# SCH_ZeeShield_-_GW_Zb_Shield_For_ESP32_E.net
KiCad netlist of a schematic drawn in EasyEDA
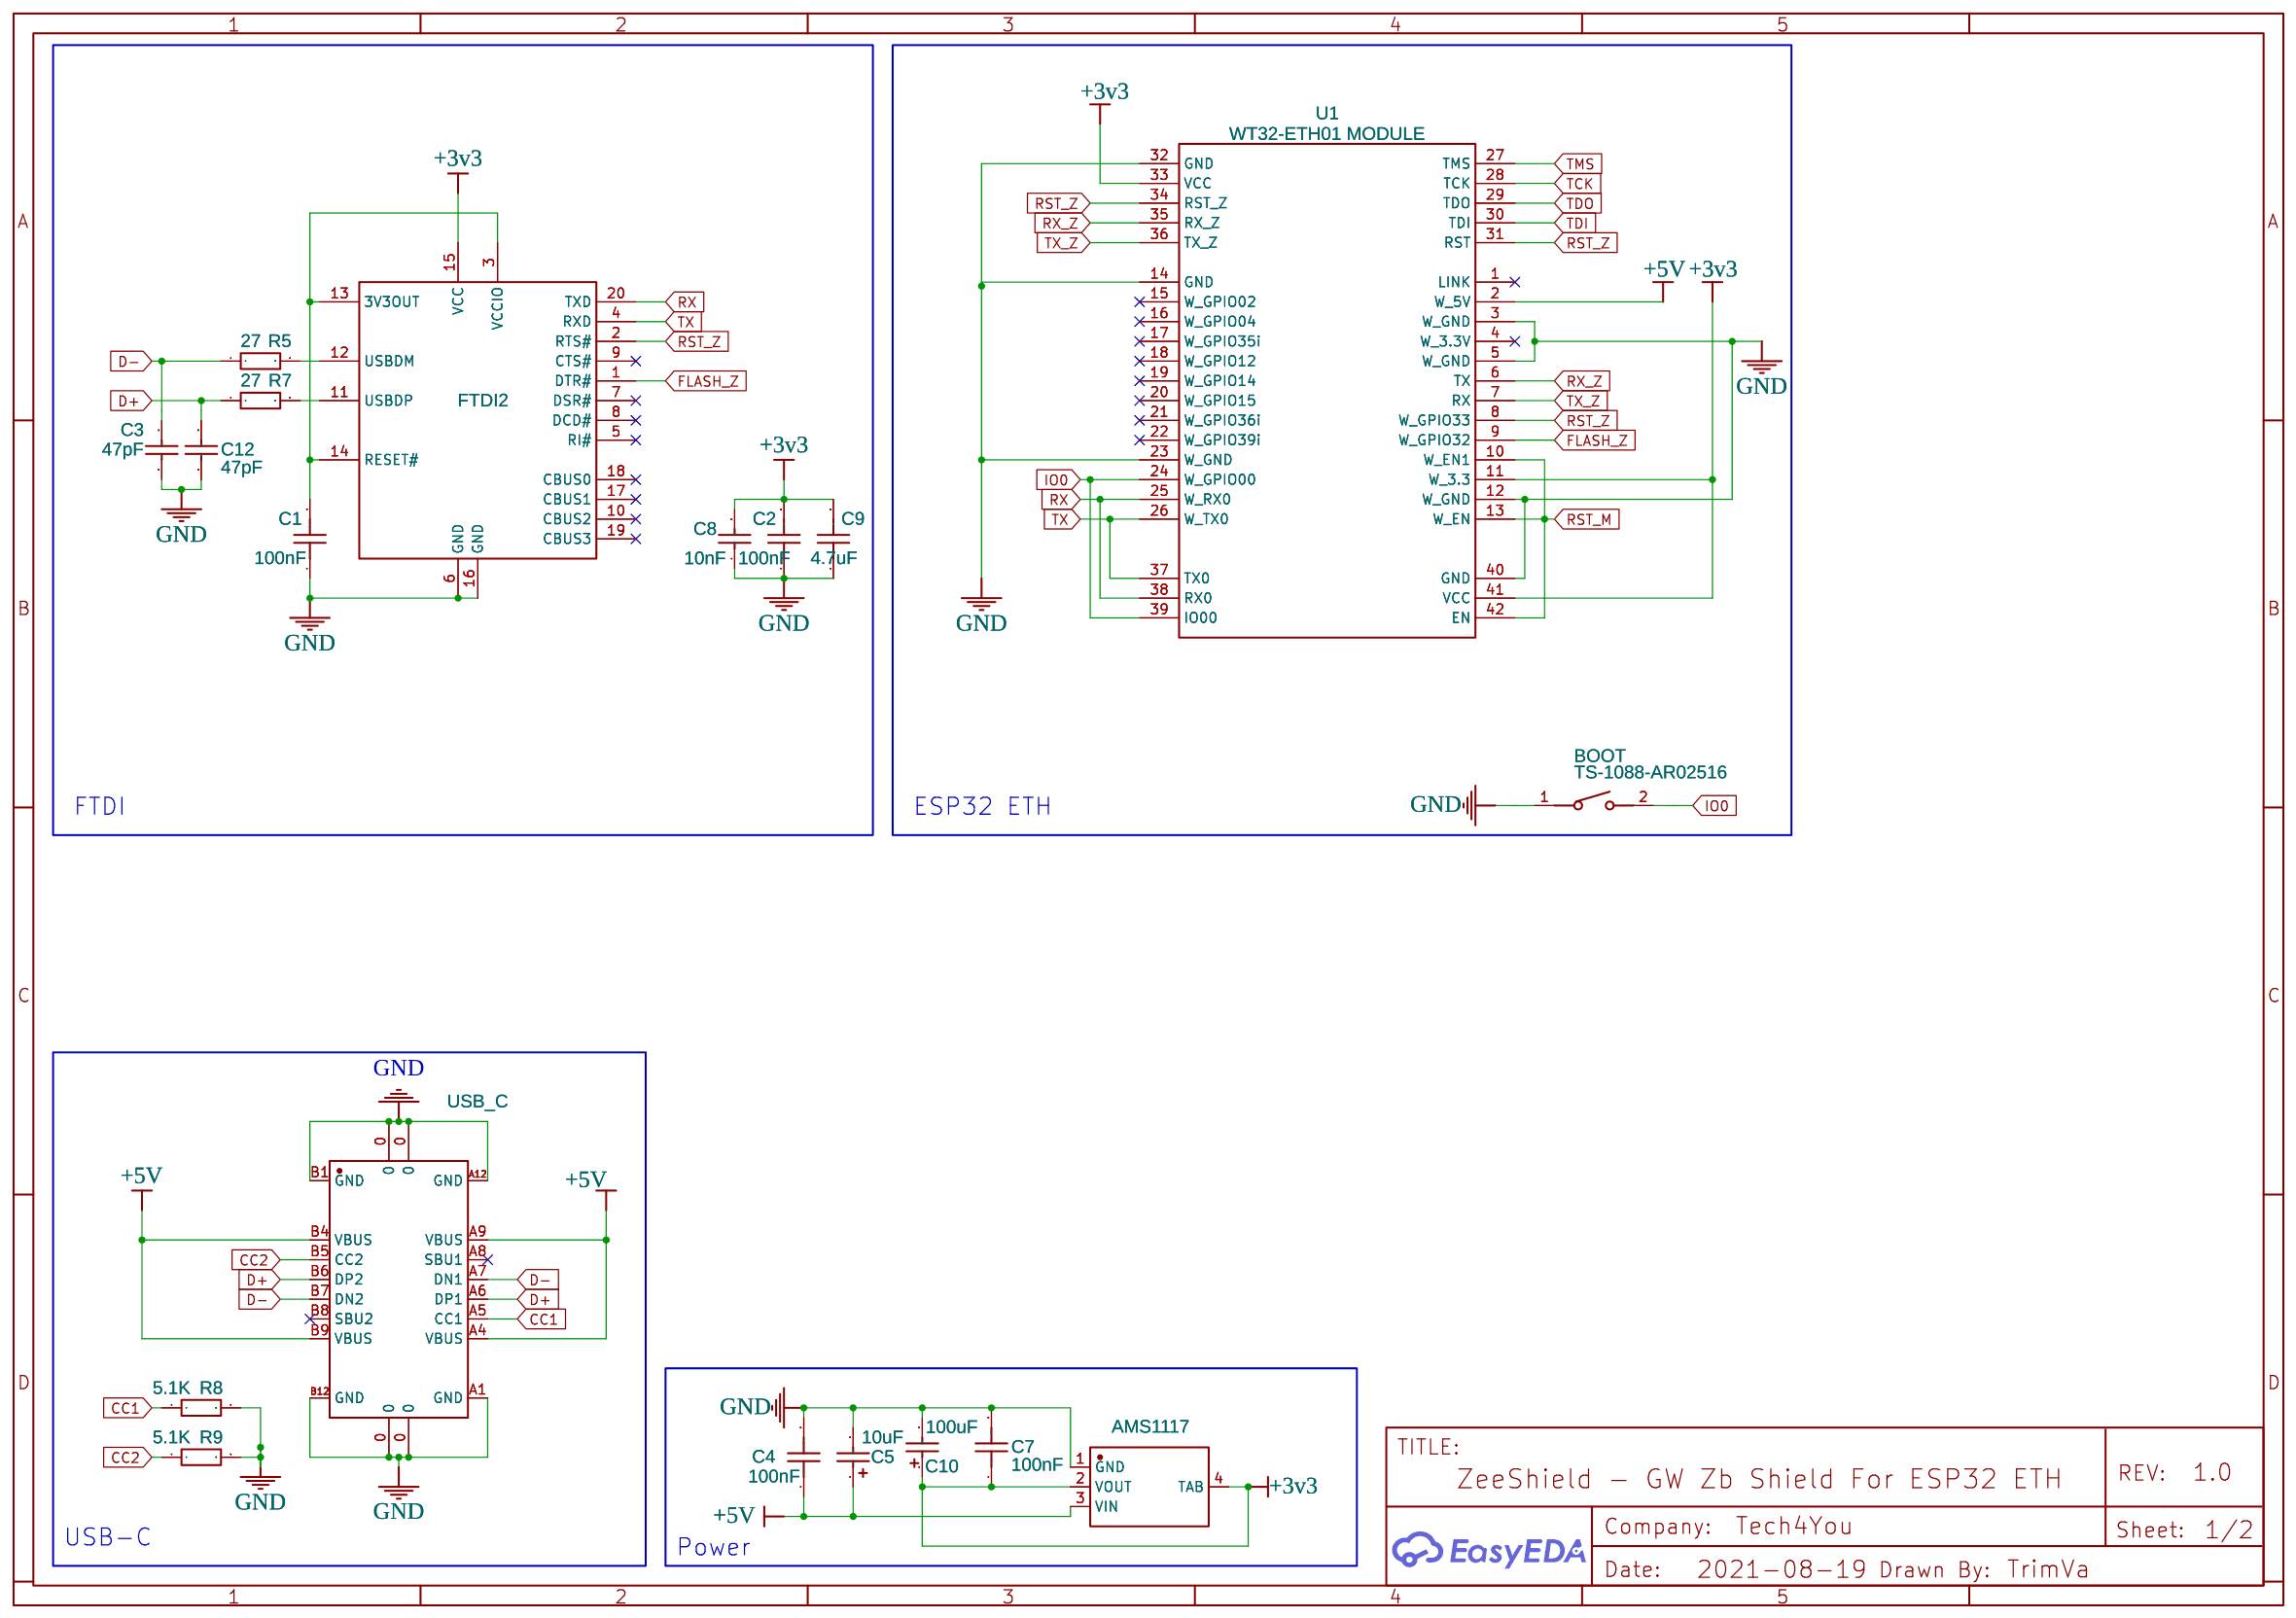
[diagram p0: Main]
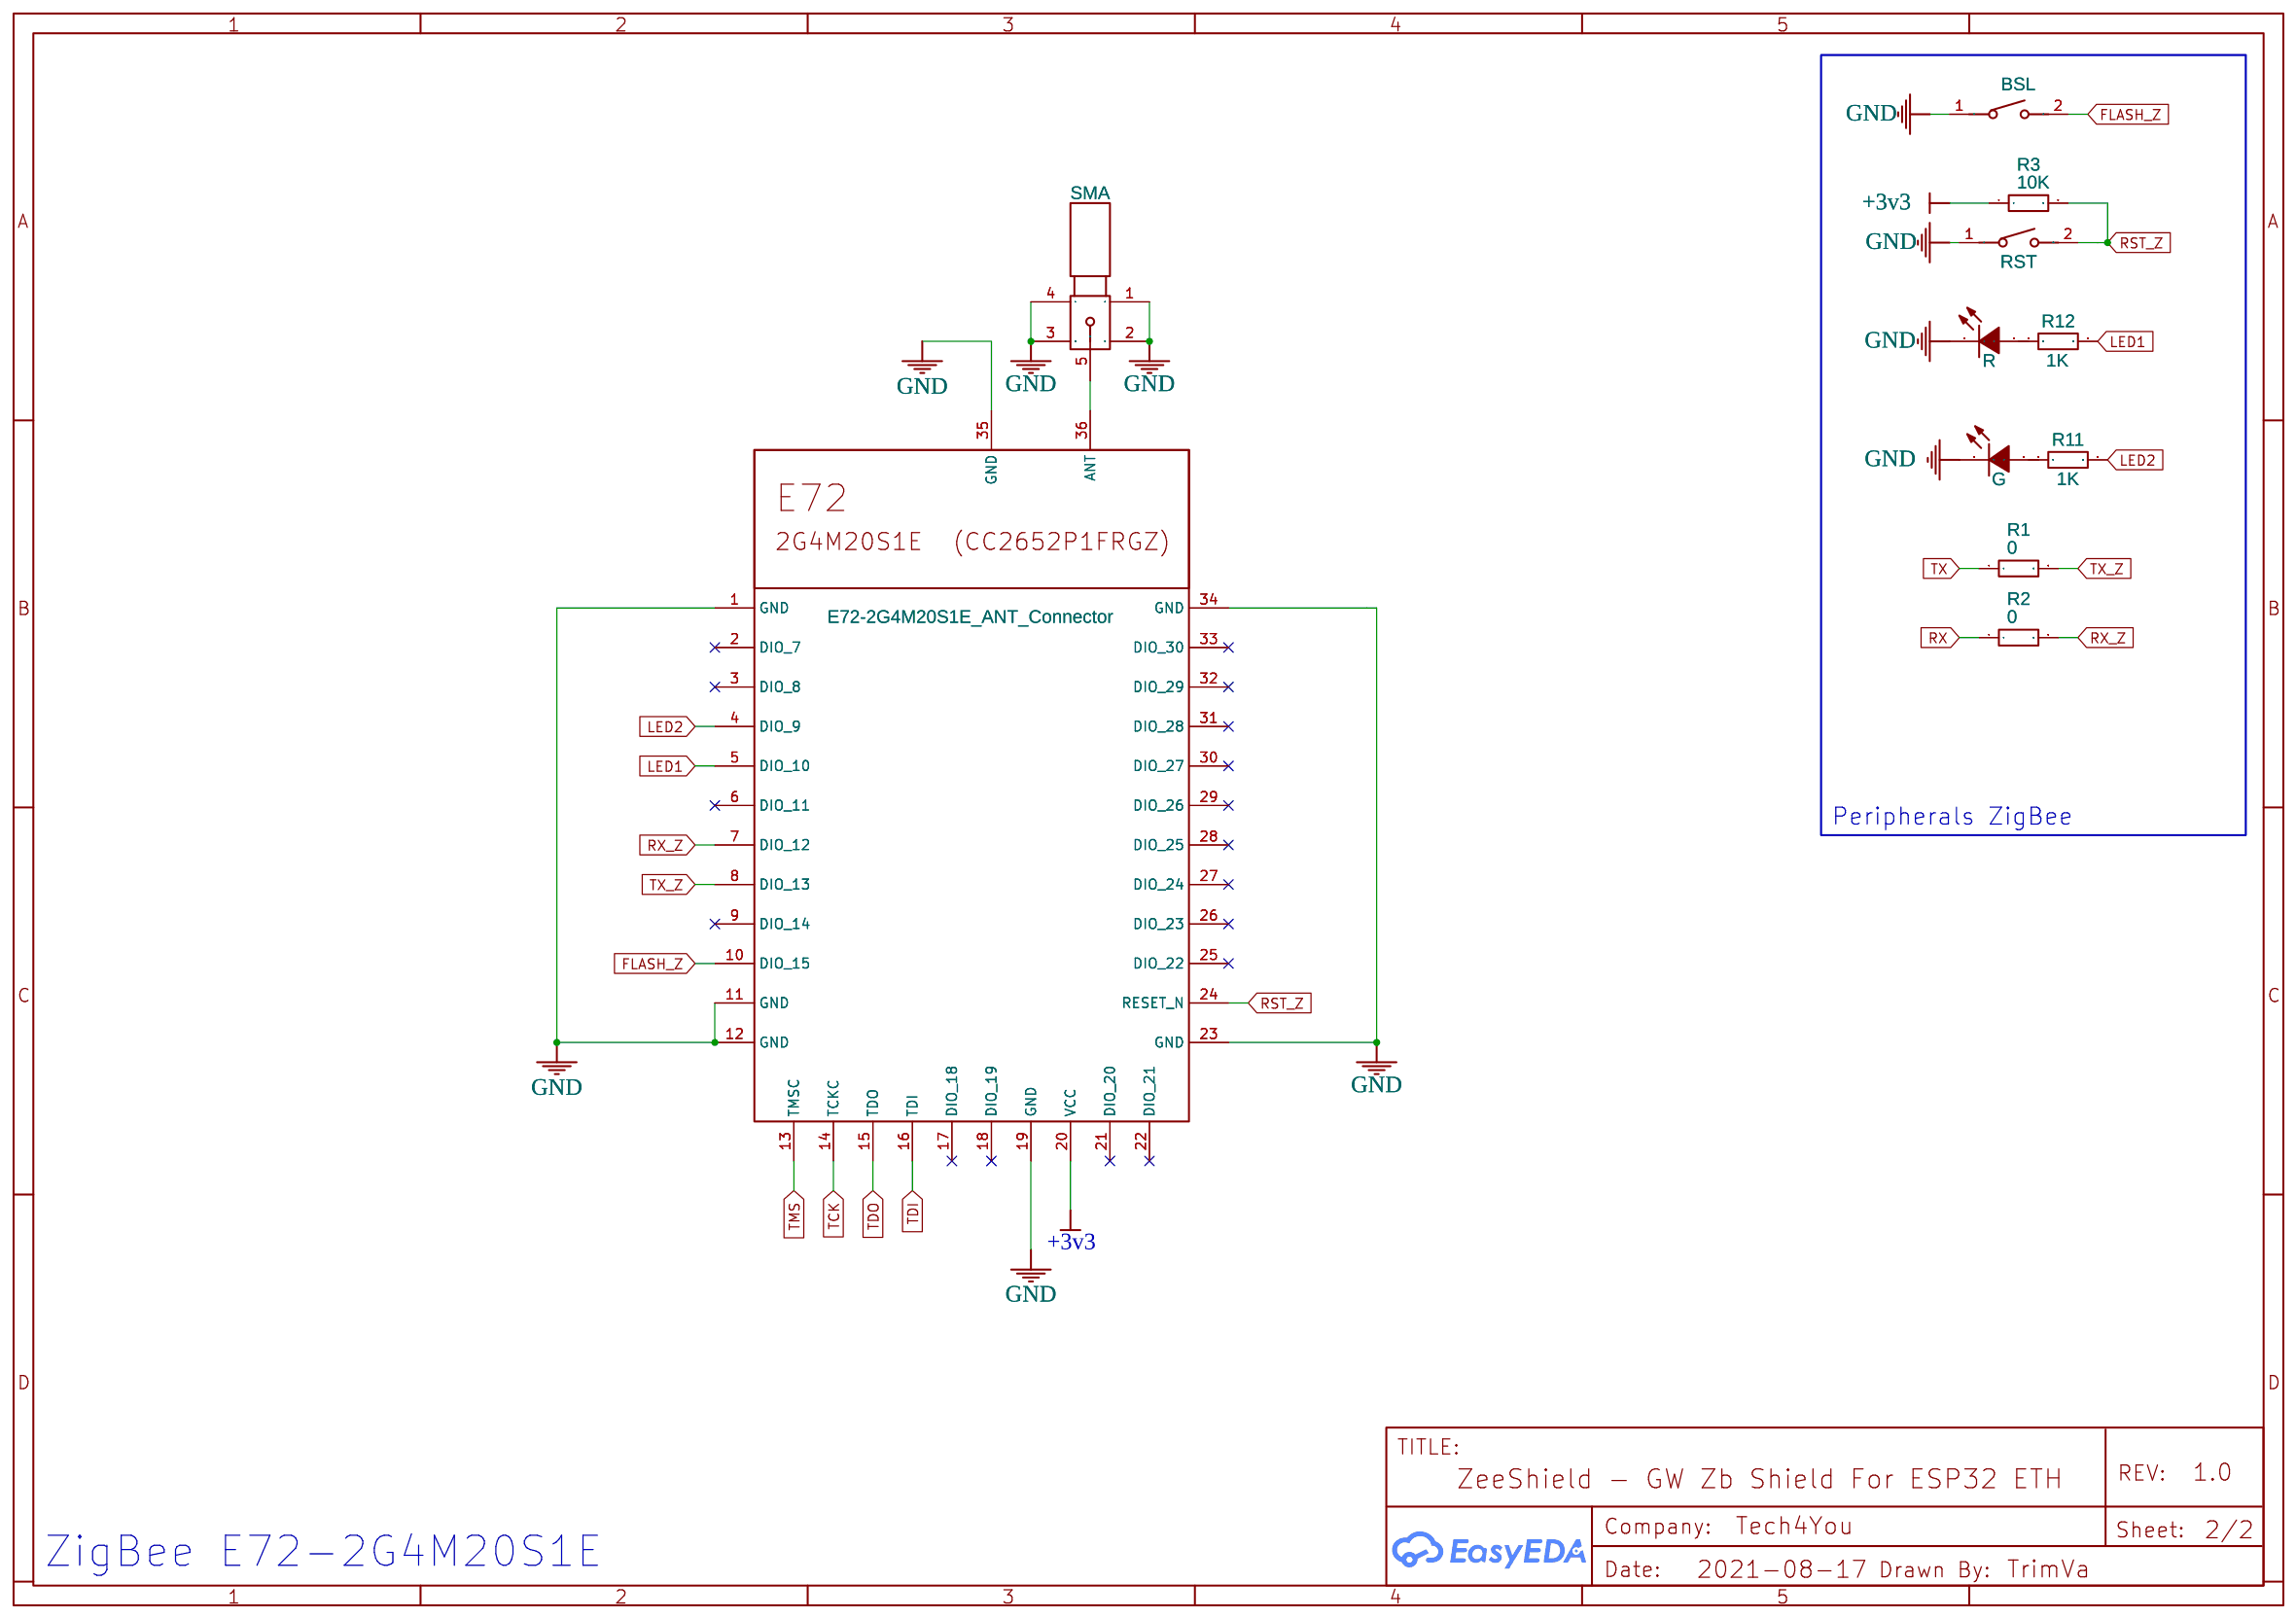
[diagram p1: ZigBee]

(export (version "E")
  (design (tool "Eeschema 10.0.6"))
  (components
    (comp (ref "AMS1117")
      (value "AMS1117-3.3_C351784")
      (fields
        (field (name "BOM_Manufacturer Part") "AMS1117-3.3")
        (field (name "BOM_Supplier Part") "C351784")
      )
      (libsource (lib "") (part "AMS1117-3.3_C351784"))
    )
    (comp (ref "BOOT")
      (value "TS-1088-AR02516")
      (fields (field (name "BOM_Supplier Part") "C720478"))
      (libsource (lib "") (part "TS-1088-AR02516"))
    )
    (comp (ref "C1")
      (value "100nF")
      (fields
        (field (name "BOM_Manufacturer Part") "TCC0402X7R104K160AT")
        (field (name "BOM_Supplier Part") "C392963")
      )
      (libsource (lib "") (part "TCC0402X7R104K160AT"))
    )
    (comp (ref "C2")
      (value "100nF")
      (fields
        (field (name "BOM_Manufacturer Part") "TCC0402X7R104K160AT")
        (field (name "BOM_Supplier Part") "C392963")
      )
      (libsource (lib "") (part "TCC0402X7R104K160AT"))
    )
    (comp (ref "C3")
      (value "47pF")
      (fields
        (field (name "BOM_Manufacturer Part") "CC0402JRNPO9BN470")
        (field (name "BOM_Supplier Part") "C60137")
      )
      (libsource (lib "") (part "CC0402JRNPO9BN470"))
    )
    (comp (ref "C4")
      (value "100nF")
      (fields
        (field (name "BOM_Manufacturer Part") "TCC0402X7R104K160AT")
        (field (name "BOM_Supplier Part") "C392963")
      )
      (libsource (lib "") (part "TCC0402X7R104K160AT"))
    )
    (comp (ref "C5")
      (value "10uF")
      (fields
        (field (name "BOM_Manufacturer Part") "TAJA106K016RNJ")
        (field (name "BOM_Supplier Part") "C7171")
      )
      (libsource (lib "") (part "TAJA106K016RNJ"))
    )
    (comp (ref "C7")
      (value "100nF")
      (fields
        (field (name "BOM_Manufacturer Part") "TCC0402X7R104K160AT")
        (field (name "BOM_Supplier Part") "C392963")
      )
      (libsource (lib "") (part "TCC0402X7R104K160AT"))
    )
    (comp (ref "C8")
      (value "10nF")
      (fields
        (field (name "BOM_Manufacturer Part") "CC0402KRX7R9BB103")
        (field (name "BOM_Supplier Part") "C60133")
      )
      (libsource (lib "") (part "CC0402KRX7R9BB103"))
    )
    (comp (ref "C9")
      (value "4.7uF")
      (fields
        (field (name "BOM_Manufacturer Part") "CL05A475MQ5NRNC")
        (field (name "BOM_Supplier Part") "C307423")
      )
      (libsource (lib "") (part "CL05A475MQ5NRNC_C307423"))
    )
    (comp (ref "C10")
      (value "100uF")
      (fields
        (field (name "BOM_Manufacturer Part") "T490A107M006ATE800")
        (field (name "BOM_Supplier Part") "C122251")
      )
      (libsource (lib "") (part "T490A107M006ATE800"))
    )
    (comp (ref "C12")
      (value "47pF")
      (fields
        (field (name "BOM_Manufacturer Part") "CC0402JRNPO9BN470")
        (field (name "BOM_Supplier Part") "C60137")
      )
      (libsource (lib "") (part "CC0402JRNPO9BN470"))
    )
    (comp (ref "FTDI2")
      (value "FT231XS-R")
      (fields (field (name "BOM_Supplier Part") "C132160"))
      (libsource (lib "") (part "FT231XS-R"))
    )
    (comp (ref "R5")
      (value "27")
      (fields
        (field (name "BOM_Manufacturer Part") "0402WGJ0270TCE")
        (field (name "BOM_Supplier Part") "C25156")
      )
      (libsource (lib "") (part "0402WGJ0270TCE"))
    )
    (comp (ref "R7")
      (value "27")
      (fields
        (field (name "BOM_Manufacturer Part") "0402WGJ0270TCE")
        (field (name "BOM_Supplier Part") "C25156")
      )
      (libsource (lib "") (part "0402WGJ0270TCE"))
    )
    (comp (ref "R8")
      (value "5.1K")
      (fields
        (field (name "BOM_Manufacturer Part") "RC-02W512JT")
        (field (name "BOM_Supplier Part") "C258132")
      )
      (libsource (lib "") (part "RC-02W512JT"))
    )
    (comp (ref "R9")
      (value "5.1K")
      (fields
        (field (name "BOM_Manufacturer Part") "RC-02W512JT")
        (field (name "BOM_Supplier Part") "C258132")
      )
      (libsource (lib "") (part "RC-02W512JT"))
    )
    (comp (ref "U1")
      (value "WT32-ETH01 MODULE")
      (fields (field (name "BOM_Manufacturer Part") "WT32-ETH01"))
      (libsource (lib "") (part "WT32-ETH01 MODULE"))
    )
    (comp (ref "USB_C")
      (value "TYPE-C-31-M-12")
      (fields (field (name "BOM_Supplier Part") "C165948"))
      (libsource (lib "") (part "TYPE-C-31-M-12"))
    )
    (comp (ref "BSL")
      (value "TS-1088-AR02516")
      (fields (field (name "BOM_Supplier Part") "C720478"))
      (libsource (lib "") (part "TS-1088-AR02516_1"))
    )
    (comp (ref "G")
      (value "G")
      (fields
        (field (name "BOM_Manufacturer Part") "0805G (Green)")
        (field (name "BOM_Supplier Part") "C2297")
      )
      (libsource (lib "") (part "0805G (Green)"))
    )
    (comp (ref "GND1")
      (value "E72-2G4M20S1E_ANT_Connector")
      (fields
        (field (name "BOM_Manufacturer Part") "CC2652P1FRGZ")
        (field (name "BOM_Supplier Part") "E72-2G4M20S1E")
      )
      (libsource (lib "") (part "E72-2G4M20S1E_ANT_Connector"))
    )
    (comp (ref "R")
      (value "R")
      (fields
        (field (name "BOM_Manufacturer Part") "FC-2012HRK-620D")
        (field (name "BOM_Supplier Part") "C84256")
      )
      (libsource (lib "") (part "FC-2012HRK-620D"))
    )
    (comp (ref "R1")
      (value "0")
      (fields
        (field (name "BOM_Manufacturer Part") "RTT02000JTH")
        (field (name "BOM_Supplier Part") "C102746")
      )
      (libsource (lib "") (part "RTT02000JTH"))
    )
    (comp (ref "R2")
      (value "0")
      (fields
        (field (name "BOM_Manufacturer Part") "RTT02000JTH")
        (field (name "BOM_Supplier Part") "C102746")
      )
      (libsource (lib "") (part "RTT02000JTH"))
    )
    (comp (ref "R3")
      (value "10K")
      (fields
        (field (name "BOM_Manufacturer Part") "RC-02W103JT")
        (field (name "BOM_Supplier Part") "C140214")
      )
      (libsource (lib "") (part "RC-02W103JT_C140214"))
    )
    (comp (ref "R11")
      (value "1K")
      (fields
        (field (name "BOM_Manufacturer Part") "0402WGF1001TCE")
        (field (name "BOM_Supplier Part") "C11702")
      )
      (libsource (lib "") (part "0402WGF1001TCE"))
    )
    (comp (ref "R12")
      (value "1K")
      (fields
        (field (name "BOM_Manufacturer Part") "0402WGF1001TCE")
        (field (name "BOM_Supplier Part") "C11702")
      )
      (libsource (lib "") (part "0402WGF1001TCE"))
    )
    (comp (ref "RST")
      (value "TS-1088-AR02516")
      (fields (field (name "BOM_Supplier Part") "C720478"))
      (libsource (lib "") (part "TS-1088-AR02516"))
    )
    (comp (ref "SMA")
      (value "BWSMA-KE-P001")
      (fields (field (name "BOM_Supplier Part") "C496550"))
      (libsource (lib "") (part "BWSMA-KE-P001"))
    )
  )
  (nets
    (net (code "1") (name "+3v3") (class "Default")
      (node (ref "AMS1117") (pin "2") (pinfunction "VOUT_2") (pintype "unspecified"))
      (node (ref "AMS1117") (pin "4") (pinfunction "TAB_4") (pintype "unspecified"))
      (node (ref "C10") (pin "1") (pinfunction "1_1") (pintype "input"))
      (node (ref "C2") (pin "2") (pinfunction "2_2") (pintype "unspecified"))
      (node (ref "C7") (pin "1") (pinfunction "1_1") (pintype "unspecified"))
      (node (ref "C8") (pin "2") (pinfunction "2_2") (pintype "input"))
      (node (ref "C9") (pin "2") (pinfunction "2_2") (pintype "unspecified"))
      (node (ref "FTDI2") (pin "15") (pinfunction "VCC_15") (pintype "passive"))
      (node (ref "GND1") (pin "20") (pinfunction "VCC_20") (pintype "unspecified"))
      (node (ref "R3") (pin "1") (pinfunction "1_1") (pintype "unspecified"))
      (node (ref "U1") (pin "11") (pinfunction "W_3.3_11") (pintype "unspecified"))
      (node (ref "U1") (pin "33") (pinfunction "VCC_33") (pintype "unspecified"))
      (node (ref "U1") (pin "41") (pinfunction "VCC_41") (pintype "unspecified"))
    )
    (net (code "2") (name "+5V") (class "Default")
      (node (ref "AMS1117") (pin "3") (pinfunction "VIN_3") (pintype "unspecified"))
      (node (ref "C4") (pin "1") (pinfunction "1_1") (pintype "unspecified"))
      (node (ref "C5") (pin "1") (pinfunction "1_1") (pintype "input"))
      (node (ref "U1") (pin "2") (pinfunction "W_5V_2") (pintype "unspecified"))
      (node (ref "USB_C") (pin "A4") (pinfunction "VBUS_A4") (pintype "unspecified"))
      (node (ref "USB_C") (pin "A9") (pinfunction "VBUS_A9") (pintype "unspecified"))
      (node (ref "USB_C") (pin "B4") (pinfunction "VBUS_B4") (pintype "unspecified"))
      (node (ref "USB_C") (pin "B9") (pinfunction "VBUS_B9") (pintype "unspecified"))
    )
    (net (code "3") (name "CC1") (class "Default")
      (node (ref "R8") (pin "1") (pinfunction "1_1") (pintype "unspecified"))
      (node (ref "USB_C") (pin "A5") (pinfunction "CC1_A5") (pintype "unspecified"))
    )
    (net (code "4") (name "CC2") (class "Default")
      (node (ref "R9") (pin "1") (pinfunction "1_1") (pintype "unspecified"))
      (node (ref "USB_C") (pin "B5") (pinfunction "CC2_B5") (pintype "unspecified"))
    )
    (net (code "5") (name "D+") (class "Default")
      (node (ref "C12") (pin "2") (pinfunction "2_2") (pintype "input"))
      (node (ref "R7") (pin "1") (pinfunction "1_1") (pintype "input"))
      (node (ref "USB_C") (pin "A6") (pinfunction "DP1_A6") (pintype "unspecified"))
      (node (ref "USB_C") (pin "B6") (pinfunction "DP2_B6") (pintype "unspecified"))
    )
    (net (code "6") (name "D-") (class "Default")
      (node (ref "C3") (pin "2") (pinfunction "2_2") (pintype "input"))
      (node (ref "R5") (pin "1") (pinfunction "1_1") (pintype "input"))
      (node (ref "USB_C") (pin "A7") (pinfunction "DN1_A7") (pintype "unspecified"))
      (node (ref "USB_C") (pin "B7") (pinfunction "DN2_B7") (pintype "unspecified"))
    )
    (net (code "7") (name "FLASH_Z") (class "Default")
      (node (ref "BSL") (pin "2") (pinfunction "2_2") (pintype "unspecified"))
      (node (ref "FTDI2") (pin "1") (pinfunction "DTR#_1") (pintype "output"))
      (node (ref "GND1") (pin "10") (pinfunction "DIO_15_10") (pintype "unspecified"))
      (node (ref "U1") (pin "9") (pinfunction "W_GPIO32_9") (pintype "unspecified"))
    )
    (net (code "8") (name "GND") (class "Default")
      (node (ref "AMS1117") (pin "1") (pinfunction "GND_1") (pintype "unspecified"))
      (node (ref "BOOT") (pin "1") (pinfunction "1_1") (pintype "unspecified"))
      (node (ref "BSL") (pin "1") (pinfunction "1_1") (pintype "unspecified"))
      (node (ref "C1") (pin "1") (pinfunction "1_1") (pintype "unspecified"))
      (node (ref "C10") (pin "2") (pinfunction "2_2") (pintype "input"))
      (node (ref "C12") (pin "1") (pinfunction "1_1") (pintype "input"))
      (node (ref "C2") (pin "1") (pinfunction "1_1") (pintype "unspecified"))
      (node (ref "C3") (pin "1") (pinfunction "1_1") (pintype "input"))
      (node (ref "C4") (pin "2") (pinfunction "2_2") (pintype "unspecified"))
      (node (ref "C5") (pin "2") (pinfunction "2_2") (pintype "input"))
      (node (ref "C7") (pin "2") (pinfunction "2_2") (pintype "unspecified"))
      (node (ref "C8") (pin "1") (pinfunction "1_1") (pintype "input"))
      (node (ref "C9") (pin "1") (pinfunction "1_1") (pintype "unspecified"))
      (node (ref "FTDI2") (pin "16") (pinfunction "GND_16") (pintype "passive"))
      (node (ref "FTDI2") (pin "6") (pinfunction "GND_6") (pintype "passive"))
      (node (ref "G") (pin "1") (pinfunction "K_1") (pintype "unspecified"))
      (node (ref "GND1") (pin "1") (pinfunction "GND_1") (pintype "unspecified"))
      (node (ref "GND1") (pin "11") (pinfunction "GND_11") (pintype "unspecified"))
      (node (ref "GND1") (pin "12") (pinfunction "GND_12") (pintype "unspecified"))
      (node (ref "GND1") (pin "19") (pinfunction "GND_19") (pintype "unspecified"))
      (node (ref "GND1") (pin "23") (pinfunction "GND_23") (pintype "unspecified"))
      (node (ref "GND1") (pin "34") (pinfunction "GND_34") (pintype "unspecified"))
      (node (ref "GND1") (pin "35") (pinfunction "GND_35") (pintype "unspecified"))
      (node (ref "R") (pin "1") (pinfunction "-_1") (pintype "unspecified"))
      (node (ref "R8") (pin "2") (pinfunction "2_2") (pintype "unspecified"))
      (node (ref "R9") (pin "2") (pinfunction "2_2") (pintype "unspecified"))
      (node (ref "RST") (pin "1") (pinfunction "1_1") (pintype "unspecified"))
      (node (ref "SMA") (pin "1") (pinfunction "1_1") (pintype "unspecified"))
      (node (ref "SMA") (pin "2") (pinfunction "2_2") (pintype "unspecified"))
      (node (ref "SMA") (pin "3") (pinfunction "3_3") (pintype "unspecified"))
      (node (ref "SMA") (pin "4") (pinfunction "4_4") (pintype "unspecified"))
      (node (ref "U1") (pin "12") (pinfunction "W_GND_12") (pintype "unspecified"))
      (node (ref "U1") (pin "14") (pinfunction "GND_14") (pintype "unspecified"))
      (node (ref "U1") (pin "23") (pinfunction "W_GND_23") (pintype "unspecified"))
      (node (ref "U1") (pin "3") (pinfunction "W_GND_3") (pintype "unspecified"))
      (node (ref "U1") (pin "32") (pinfunction "GND_32") (pintype "unspecified"))
      (node (ref "U1") (pin "40") (pinfunction "GND_40") (pintype "unspecified"))
      (node (ref "U1") (pin "5") (pinfunction "W_GND_5") (pintype "unspecified"))
      (node (ref "USB_C") (pin "0") (pinfunction "0_0") (pintype "unspecified"))
      (node (ref "USB_C") (pin "A1") (pinfunction "GND_A1") (pintype "unspecified"))
      (node (ref "USB_C") (pin "A12") (pinfunction "GND_A12") (pintype "unspecified"))
      (node (ref "USB_C") (pin "B1") (pinfunction "GND_B1") (pintype "unspecified"))
      (node (ref "USB_C") (pin "B12") (pinfunction "GND_B12") (pintype "unspecified"))
    )
    (net (code "9") (name "IO0") (class "Default")
      (node (ref "BOOT") (pin "2") (pinfunction "2_2") (pintype "unspecified"))
      (node (ref "U1") (pin "24") (pinfunction "W_GPIO00_24") (pintype "unspecified"))
      (node (ref "U1") (pin "39") (pinfunction "IO00_39") (pintype "unspecified"))
    )
    (net (code "10") (name "LED1") (class "Default")
      (node (ref "GND1") (pin "5") (pinfunction "DIO_10_5") (pintype "unspecified"))
      (node (ref "R12") (pin "2") (pinfunction "2_2") (pintype "input"))
    )
    (net (code "11") (name "LED2") (class "Default")
      (node (ref "GND1") (pin "4") (pinfunction "DIO_9_4") (pintype "unspecified"))
      (node (ref "R11") (pin "2") (pinfunction "2_2") (pintype "input"))
    )
    (net (code "12") (name "Net-(FTDI2-3V3OUT)") (class "Default")
      (node (ref "C1") (pin "2") (pinfunction "2_2") (pintype "unspecified"))
      (node (ref "FTDI2") (pin "13") (pinfunction "3V3OUT_13") (pintype "passive"))
      (node (ref "FTDI2") (pin "14") (pinfunction "RESET#_14") (pintype "unspecified"))
      (node (ref "FTDI2") (pin "3") (pinfunction "VCCIO_3") (pintype "passive"))
    )
    (net (code "13") (name "Net-(FTDI2-USBDM)") (class "Default")
      (node (ref "FTDI2") (pin "12") (pinfunction "USBDM_12") (pintype "unspecified"))
      (node (ref "R5") (pin "2") (pinfunction "2_2") (pintype "input"))
    )
    (net (code "14") (name "Net-(FTDI2-USBDP)") (class "Default")
      (node (ref "FTDI2") (pin "11") (pinfunction "USBDP_11") (pintype "unspecified"))
      (node (ref "R7") (pin "2") (pinfunction "2_2") (pintype "input"))
    )
    (net (code "15") (name "Net-(G-A)") (class "Default")
      (node (ref "G") (pin "2") (pinfunction "A_2") (pintype "unspecified"))
      (node (ref "R11") (pin "1") (pinfunction "1_1") (pintype "input"))
    )
    (net (code "16") (name "Net-(GND1-ANT)") (class "Default")
      (node (ref "GND1") (pin "36") (pinfunction "ANT_36") (pintype "unspecified"))
      (node (ref "SMA") (pin "5") (pinfunction "5_5") (pintype "unspecified"))
    )
    (net (code "17") (name "Net-(R-+)") (class "Default")
      (node (ref "R") (pin "2") (pinfunction "+_2") (pintype "unspecified"))
      (node (ref "R12") (pin "1") (pinfunction "1_1") (pintype "input"))
    )
    (net (code "18") (name "RST_M") (class "Default")
      (node (ref "U1") (pin "10") (pinfunction "W_EN1_10") (pintype "unspecified"))
      (node (ref "U1") (pin "13") (pinfunction "W_EN_13") (pintype "unspecified"))
      (node (ref "U1") (pin "42") (pinfunction "EN_42") (pintype "unspecified"))
    )
    (net (code "19") (name "RST_Z") (class "Default")
      (node (ref "FTDI2") (pin "2") (pinfunction "RTS#_2") (pintype "output"))
      (node (ref "GND1") (pin "24") (pinfunction "RESET_N_24") (pintype "unspecified"))
      (node (ref "R3") (pin "2") (pinfunction "2_2") (pintype "unspecified"))
      (node (ref "RST") (pin "2") (pinfunction "2_2") (pintype "unspecified"))
      (node (ref "U1") (pin "31") (pinfunction "RST_31") (pintype "unspecified"))
      (node (ref "U1") (pin "34") (pinfunction "RST_Z_34") (pintype "unspecified"))
      (node (ref "U1") (pin "8") (pinfunction "W_GPIO33_8") (pintype "unspecified"))
    )
    (net (code "20") (name "RX") (class "Default")
      (node (ref "FTDI2") (pin "20") (pinfunction "TXD_20") (pintype "output"))
      (node (ref "R2") (pin "1") (pinfunction "1_1") (pintype "input"))
      (node (ref "U1") (pin "25") (pinfunction "W_RX0_25") (pintype "unspecified"))
      (node (ref "U1") (pin "38") (pinfunction "RX0_38") (pintype "unspecified"))
    )
    (net (code "21") (name "RX_Z") (class "Default")
      (node (ref "GND1") (pin "7") (pinfunction "DIO_12_7") (pintype "unspecified"))
      (node (ref "R2") (pin "2") (pinfunction "2_2") (pintype "input"))
      (node (ref "U1") (pin "35") (pinfunction "RX_Z_35") (pintype "unspecified"))
      (node (ref "U1") (pin "6") (pinfunction "TX_6") (pintype "unspecified"))
    )
    (net (code "22") (name "TCK") (class "Default")
      (node (ref "GND1") (pin "14") (pinfunction "TCKC_14") (pintype "unspecified"))
      (node (ref "U1") (pin "28") (pinfunction "TCK_28") (pintype "unspecified"))
    )
    (net (code "23") (name "TDI") (class "Default")
      (node (ref "GND1") (pin "16") (pinfunction "TDI_16") (pintype "unspecified"))
      (node (ref "U1") (pin "30") (pinfunction "TDI_30") (pintype "unspecified"))
    )
    (net (code "24") (name "TDO") (class "Default")
      (node (ref "GND1") (pin "15") (pinfunction "TDO_15") (pintype "unspecified"))
      (node (ref "U1") (pin "29") (pinfunction "TDO_29") (pintype "unspecified"))
    )
    (net (code "25") (name "TMS") (class "Default")
      (node (ref "GND1") (pin "13") (pinfunction "TMSC_13") (pintype "unspecified"))
      (node (ref "U1") (pin "27") (pinfunction "TMS_27") (pintype "unspecified"))
    )
    (net (code "26") (name "TX") (class "Default")
      (node (ref "FTDI2") (pin "4") (pinfunction "RXD_4") (pintype "unspecified"))
      (node (ref "R1") (pin "1") (pinfunction "1_1") (pintype "input"))
      (node (ref "U1") (pin "26") (pinfunction "W_TX0_26") (pintype "unspecified"))
      (node (ref "U1") (pin "37") (pinfunction "TX0_37") (pintype "unspecified"))
    )
    (net (code "27") (name "TX_Z") (class "Default")
      (node (ref "GND1") (pin "8") (pinfunction "DIO_13_8") (pintype "unspecified"))
      (node (ref "R1") (pin "2") (pinfunction "2_2") (pintype "input"))
      (node (ref "U1") (pin "36") (pinfunction "TX_Z_36") (pintype "unspecified"))
      (node (ref "U1") (pin "7") (pinfunction "RX_7") (pintype "unspecified"))
    )
    (net (code "28") (name "unconnected-(FTDI2-CBUS0-Pad18)") (class "Default")
      (node (ref "FTDI2") (pin "18") (pinfunction "CBUS0_18") (pintype "bidirectional+no_connect"))
    )
    (net (code "29") (name "unconnected-(FTDI2-CBUS1-Pad17)") (class "Default")
      (node (ref "FTDI2") (pin "17") (pinfunction "CBUS1_17") (pintype "bidirectional+no_connect"))
    )
    (net (code "30") (name "unconnected-(FTDI2-CBUS2-Pad10)") (class "Default")
      (node (ref "FTDI2") (pin "10") (pinfunction "CBUS2_10") (pintype "bidirectional+no_connect"))
    )
    (net (code "31") (name "unconnected-(FTDI2-CBUS3-Pad19)") (class "Default")
      (node (ref "FTDI2") (pin "19") (pinfunction "CBUS3_19") (pintype "bidirectional+no_connect"))
    )
    (net (code "32") (name "unconnected-(FTDI2-CTS#-Pad9)") (class "Default")
      (node (ref "FTDI2") (pin "9") (pinfunction "CTS#_9") (pintype "unspecified+no_connect"))
    )
    (net (code "33") (name "unconnected-(FTDI2-DCD#-Pad8)") (class "Default")
      (node (ref "FTDI2") (pin "8") (pinfunction "DCD#_8") (pintype "unspecified+no_connect"))
    )
    (net (code "34") (name "unconnected-(FTDI2-DSR#-Pad7)") (class "Default")
      (node (ref "FTDI2") (pin "7") (pinfunction "DSR#_7") (pintype "unspecified+no_connect"))
    )
    (net (code "35") (name "unconnected-(FTDI2-RI#-Pad5)") (class "Default")
      (node (ref "FTDI2") (pin "5") (pinfunction "RI#_5") (pintype "unspecified+no_connect"))
    )
    (net (code "36") (name "unconnected-(GND1-DIO_7-Pad2)") (class "Default")
      (node (ref "GND1") (pin "2") (pinfunction "DIO_7_2") (pintype "unspecified+no_connect"))
    )
    (net (code "37") (name "unconnected-(GND1-DIO_8-Pad3)") (class "Default")
      (node (ref "GND1") (pin "3") (pinfunction "DIO_8_3") (pintype "unspecified+no_connect"))
    )
    (net (code "38") (name "unconnected-(GND1-DIO_11-Pad6)") (class "Default")
      (node (ref "GND1") (pin "6") (pinfunction "DIO_11_6") (pintype "unspecified+no_connect"))
    )
    (net (code "39") (name "unconnected-(GND1-DIO_14-Pad9)") (class "Default")
      (node (ref "GND1") (pin "9") (pinfunction "DIO_14_9") (pintype "unspecified+no_connect"))
    )
    (net (code "40") (name "unconnected-(GND1-DIO_18-Pad17)") (class "Default")
      (node (ref "GND1") (pin "17") (pinfunction "DIO_18_17") (pintype "unspecified+no_connect"))
    )
    (net (code "41") (name "unconnected-(GND1-DIO_19-Pad18)") (class "Default")
      (node (ref "GND1") (pin "18") (pinfunction "DIO_19_18") (pintype "unspecified+no_connect"))
    )
    (net (code "42") (name "unconnected-(GND1-DIO_20-Pad21)") (class "Default")
      (node (ref "GND1") (pin "21") (pinfunction "DIO_20_21") (pintype "unspecified+no_connect"))
    )
    (net (code "43") (name "unconnected-(GND1-DIO_21-Pad22)") (class "Default")
      (node (ref "GND1") (pin "22") (pinfunction "DIO_21_22") (pintype "unspecified+no_connect"))
    )
    (net (code "44") (name "unconnected-(GND1-DIO_22-Pad25)") (class "Default")
      (node (ref "GND1") (pin "25") (pinfunction "DIO_22_25") (pintype "unspecified+no_connect"))
    )
    (net (code "45") (name "unconnected-(GND1-DIO_23-Pad26)") (class "Default")
      (node (ref "GND1") (pin "26") (pinfunction "DIO_23_26") (pintype "unspecified+no_connect"))
    )
    (net (code "46") (name "unconnected-(GND1-DIO_24-Pad27)") (class "Default")
      (node (ref "GND1") (pin "27") (pinfunction "DIO_24_27") (pintype "unspecified+no_connect"))
    )
    (net (code "47") (name "unconnected-(GND1-DIO_25-Pad28)") (class "Default")
      (node (ref "GND1") (pin "28") (pinfunction "DIO_25_28") (pintype "unspecified+no_connect"))
    )
    (net (code "48") (name "unconnected-(GND1-DIO_26-Pad29)") (class "Default")
      (node (ref "GND1") (pin "29") (pinfunction "DIO_26_29") (pintype "unspecified+no_connect"))
    )
    (net (code "49") (name "unconnected-(GND1-DIO_27-Pad30)") (class "Default")
      (node (ref "GND1") (pin "30") (pinfunction "DIO_27_30") (pintype "unspecified+no_connect"))
    )
    (net (code "50") (name "unconnected-(GND1-DIO_28-Pad31)") (class "Default")
      (node (ref "GND1") (pin "31") (pinfunction "DIO_28_31") (pintype "unspecified+no_connect"))
    )
    (net (code "51") (name "unconnected-(GND1-DIO_29-Pad32)") (class "Default")
      (node (ref "GND1") (pin "32") (pinfunction "DIO_29_32") (pintype "unspecified+no_connect"))
    )
    (net (code "52") (name "unconnected-(GND1-DIO_30-Pad33)") (class "Default")
      (node (ref "GND1") (pin "33") (pinfunction "DIO_30_33") (pintype "unspecified+no_connect"))
    )
    (net (code "53") (name "unconnected-(U1-LINK-Pad1)") (class "Default")
      (node (ref "U1") (pin "1") (pinfunction "LINK_1") (pintype "unspecified+no_connect"))
    )
    (net (code "54") (name "unconnected-(U1-W_3.3V-Pad4)") (class "Default")
      (node (ref "U1") (pin "4") (pinfunction "W_3.3V_4") (pintype "unspecified+no_connect"))
    )
    (net (code "55") (name "unconnected-(U1-W_GPIO02-Pad15)") (class "Default")
      (node (ref "U1") (pin "15") (pinfunction "W_GPIO02_15") (pintype "unspecified+no_connect"))
    )
    (net (code "56") (name "unconnected-(U1-W_GPIO04-Pad16)") (class "Default")
      (node (ref "U1") (pin "16") (pinfunction "W_GPIO04_16") (pintype "unspecified+no_connect"))
    )
    (net (code "57") (name "unconnected-(U1-W_GPIO12-Pad18)") (class "Default")
      (node (ref "U1") (pin "18") (pinfunction "W_GPIO12_18") (pintype "unspecified+no_connect"))
    )
    (net (code "58") (name "unconnected-(U1-W_GPIO14-Pad19)") (class "Default")
      (node (ref "U1") (pin "19") (pinfunction "W_GPIO14_19") (pintype "unspecified+no_connect"))
    )
    (net (code "59") (name "unconnected-(U1-W_GPIO15-Pad20)") (class "Default")
      (node (ref "U1") (pin "20") (pinfunction "W_GPIO15_20") (pintype "unspecified+no_connect"))
    )
    (net (code "60") (name "unconnected-(U1-W_GPIO35i-Pad17)") (class "Default")
      (node (ref "U1") (pin "17") (pinfunction "W_GPIO35i_17") (pintype "unspecified+no_connect"))
    )
    (net (code "61") (name "unconnected-(U1-W_GPIO36i-Pad21)") (class "Default")
      (node (ref "U1") (pin "21") (pinfunction "W_GPIO36i_21") (pintype "unspecified+no_connect"))
    )
    (net (code "62") (name "unconnected-(U1-W_GPIO39i-Pad22)") (class "Default")
      (node (ref "U1") (pin "22") (pinfunction "W_GPIO39i_22") (pintype "unspecified+no_connect"))
    )
    (net (code "63") (name "unconnected-(USB_C-SBU1-PadA8)") (class "Default")
      (node (ref "USB_C") (pin "A8") (pinfunction "SBU1_A8") (pintype "unspecified+no_connect"))
    )
    (net (code "64") (name "unconnected-(USB_C-SBU2-PadB8)") (class "Default")
      (node (ref "USB_C") (pin "B8") (pinfunction "SBU2_B8") (pintype "unspecified+no_connect"))
    )
  )
)
